# W25Q128.net
KiCad netlist of a schematic drawn in Altium Designer
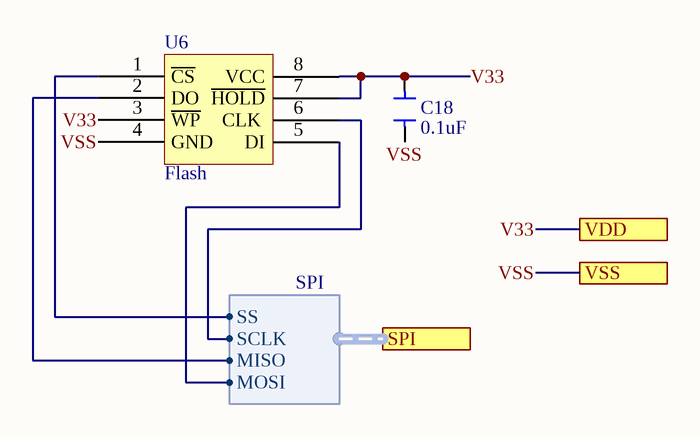
[diagram p0: W25Q128.SchDoc]

(export (version "E")
  (design (tool "Eeschema 10.0.6"))
  (components
    (comp (ref "C18")
      (value "0.1uF")
      (footprint "CAP_0402")
      (fields (field (name "Comment") "Cap"))
      (libsource (lib "ZGR") (part "Cap"))
    )
    (comp (ref "U6") (value "Flash") (footprint "8-Pin SOIC 208-mil") (libsource (lib "ZGR") (part "W25QXX")))
  )
  (nets
    (net (code "2") (name "/MISO") (class "Default")
      (node (ref "U6") (pin "2") (pinfunction "DO_2") (pintype "passive"))
    )
    (net (code "3") (name "/MOSI") (class "Default")
      (node (ref "U6") (pin "5") (pinfunction "DI_5") (pintype "passive"))
    )
    (net (code "4") (name "/SCLK") (class "Default")
      (node (ref "U6") (pin "6") (pinfunction "CLK_6") (pintype "passive"))
    )
    (net (code "5") (name "/SS") (class "Default")
      (node (ref "U6") (pin "1") (pinfunction "~{CS}_1") (pintype "passive"))
    )
    (net (code "6") (name "/V33") (class "Default")
      (node (ref "C18") (pin "1") (pinfunction "1_1") (pintype "passive"))
      (node (ref "U6") (pin "3") (pinfunction "~{WP}_3") (pintype "passive"))
      (node (ref "U6") (pin "7") (pinfunction "~{HOLD}_7") (pintype "passive"))
      (node (ref "U6") (pin "8") (pinfunction "VCC_8") (pintype "passive"))
    )
    (net (code "7") (name "/VSS") (class "Default")
      (node (ref "C18") (pin "2") (pinfunction "2_2") (pintype "passive"))
      (node (ref "U6") (pin "4") (pinfunction "GND_4") (pintype "passive"))
    )
  )
)
